# untitled.net
KiCad netlist of a schematic drawn in EAGLE
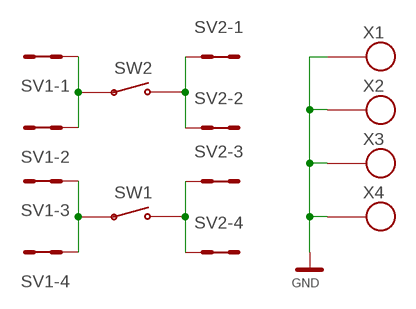
[diagram p0: schematic, sheet 1]

(export (version "E")
  (design (tool "Eeschema 10.0.6"))
  (components
    (comp (ref "SV1")
      (value "MA04-2")
      (footprint "eagle-import:MA04-2")
      (libsource (lib "eagle-import") (part "MA04-2"))
    )
    (comp (ref "SV2")
      (value "MA04-2")
      (footprint "eagle-import:MA04-2")
      (libsource (lib "eagle-import") (part "MA04-2"))
    )
    (comp (ref "SW1")
      (value "TACT-64K")
      (footprint "eagle-import:TACT-64K")
      (libsource (lib "eagle-import") (part "TACT-64K"))
    )
    (comp (ref "SW2")
      (value "TACT-64K")
      (footprint "eagle-import:TACT-64K")
      (libsource (lib "eagle-import") (part "TACT-64K"))
    )
    (comp (ref "X1")
      (value "SROUB3M")
      (footprint "eagle-import:SROUB3M")
      (libsource (lib "eagle-import") (part "SROUB3M"))
    )
    (comp (ref "X2")
      (value "SROUB3M")
      (footprint "eagle-import:SROUB3M")
      (libsource (lib "eagle-import") (part "SROUB3M"))
    )
    (comp (ref "X3")
      (value "SROUB3M")
      (footprint "eagle-import:SROUB3M")
      (libsource (lib "eagle-import") (part "SROUB3M"))
    )
    (comp (ref "X4")
      (value "SROUB3M")
      (footprint "eagle-import:SROUB3M")
      (libsource (lib "eagle-import") (part "SROUB3M"))
    )
  )
  (nets
    (net (code "1") (name "GND") (class "Default")
      (node (ref "X1") (pin "P$1") (pinfunction "P$1_P$1") (pintype "bidirectional"))
      (node (ref "X2") (pin "P$1") (pinfunction "P$1_P$1") (pintype "bidirectional"))
      (node (ref "X3") (pin "P$1") (pinfunction "P$1_P$1") (pintype "bidirectional"))
      (node (ref "X4") (pin "P$1") (pinfunction "P$1_P$1") (pintype "bidirectional"))
    )
    (net (code "2") (name "Net-(SV1A-K-Pad1)") (class "Default")
      (node (ref "SV1") (pin "1") (pinfunction "K_1") (pintype "passive"))
      (node (ref "SV1") (pin "2") (pinfunction "K_2") (pintype "passive"))
      (node (ref "SV1") (pin "3") (pinfunction "K_3") (pintype "passive"))
      (node (ref "SV1") (pin "4") (pinfunction "K_4") (pintype "passive"))
      (node (ref "SW2") (pin "P$1") (pinfunction "P$1_P$1") (pintype "passive"))
      (node (ref "SW2") (pin "P$2") (pinfunction "P$1_P$2") (pintype "passive"))
    )
    (net (code "3") (name "Net-(SV1C-K-Pad5)") (class "Default")
      (node (ref "SV1") (pin "5") (pinfunction "K_5") (pintype "passive"))
      (node (ref "SV1") (pin "6") (pinfunction "K_6") (pintype "passive"))
      (node (ref "SV1") (pin "7") (pinfunction "K_7") (pintype "passive"))
      (node (ref "SV1") (pin "8") (pinfunction "K_8") (pintype "passive"))
      (node (ref "SW1") (pin "P$1") (pinfunction "P$1_P$1") (pintype "passive"))
      (node (ref "SW1") (pin "P$2") (pinfunction "P$1_P$2") (pintype "passive"))
    )
    (net (code "4") (name "Net-(SV2A-K-Pad1)") (class "Default")
      (node (ref "SV2") (pin "1") (pinfunction "K_1") (pintype "passive"))
      (node (ref "SV2") (pin "2") (pinfunction "K_2") (pintype "passive"))
      (node (ref "SV2") (pin "3") (pinfunction "K_3") (pintype "passive"))
      (node (ref "SV2") (pin "4") (pinfunction "K_4") (pintype "passive"))
      (node (ref "SW2") (pin "P$3") (pinfunction "P$2_P$3") (pintype "passive"))
      (node (ref "SW2") (pin "P$4") (pinfunction "P$2_P$4") (pintype "passive"))
    )
    (net (code "5") (name "Net-(SV2C-K-Pad5)") (class "Default")
      (node (ref "SV2") (pin "5") (pinfunction "K_5") (pintype "passive"))
      (node (ref "SV2") (pin "6") (pinfunction "K_6") (pintype "passive"))
      (node (ref "SV2") (pin "7") (pinfunction "K_7") (pintype "passive"))
      (node (ref "SV2") (pin "8") (pinfunction "K_8") (pintype "passive"))
      (node (ref "SW1") (pin "P$3") (pinfunction "P$2_P$3") (pintype "passive"))
      (node (ref "SW1") (pin "P$4") (pinfunction "P$2_P$4") (pintype "passive"))
    )
  )
)
